# canusb.net
KiCad netlist of a schematic drawn in EAGLE
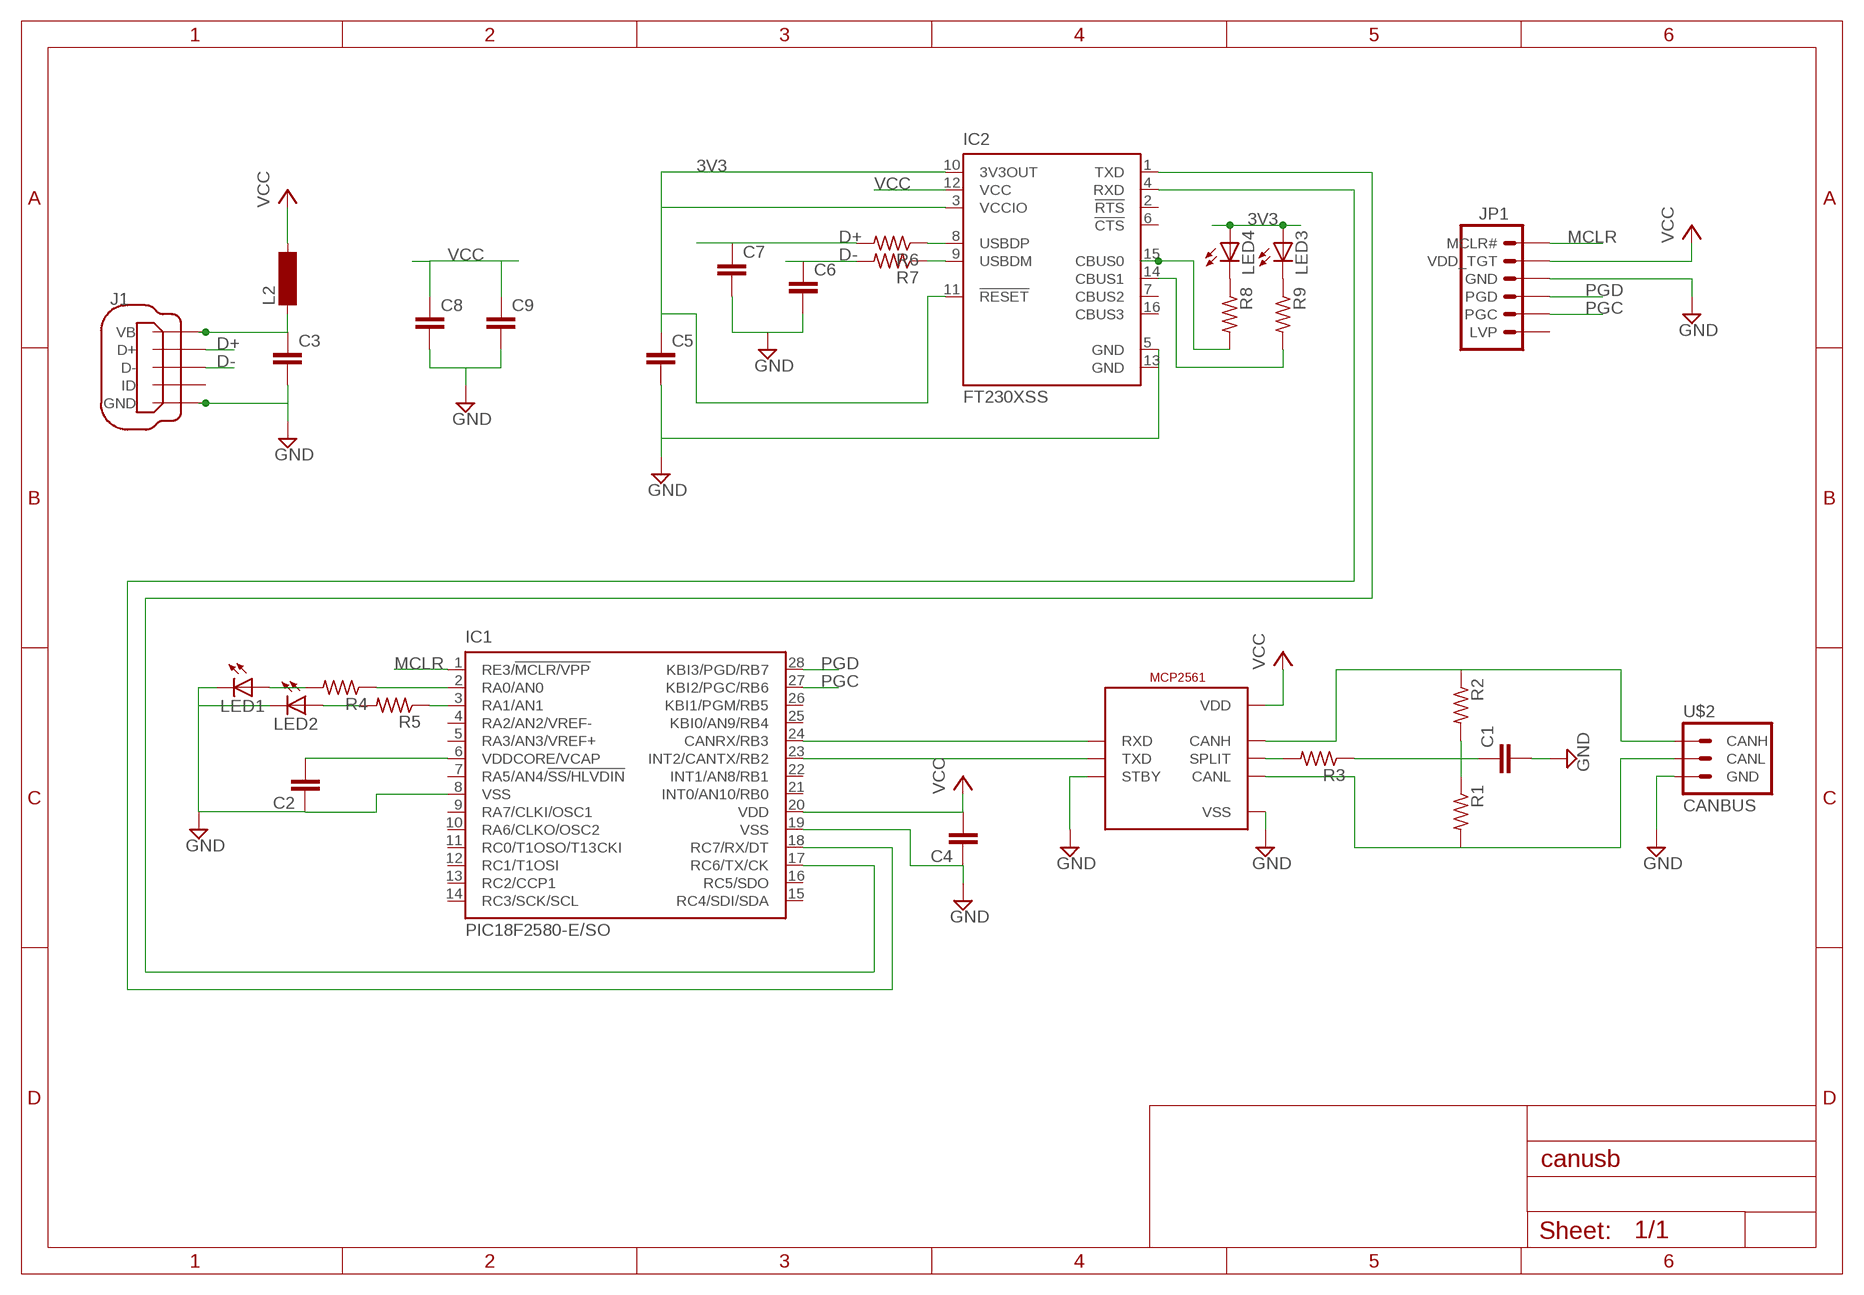
[diagram p0: schematic, sheet 1]

(export (version "E")
  (design (tool "Eeschema 10.0.6"))
  (components
    (comp (ref "C1")
      (value "C-EUC0805K")
      (footprint "eagle-import:C0805K")
      (libsource (lib "eagle-import") (part "C-EUC0805K"))
    )
    (comp (ref "C2")
      (value "C-EUC0805K")
      (footprint "eagle-import:C0805K")
      (libsource (lib "eagle-import") (part "C-EUC0805K"))
    )
    (comp (ref "C3")
      (value "C-EUC0805K")
      (footprint "eagle-import:C0805K")
      (libsource (lib "eagle-import") (part "C-EUC0805K"))
    )
    (comp (ref "C4")
      (value "C-EUC0805K")
      (footprint "eagle-import:C0805K")
      (libsource (lib "eagle-import") (part "C-EUC0805K"))
    )
    (comp (ref "C5")
      (value "C-EUC0805K")
      (footprint "eagle-import:C0805K")
      (libsource (lib "eagle-import") (part "C-EUC0805K"))
    )
    (comp (ref "C6")
      (value "C-EUC0805K")
      (footprint "eagle-import:C0805K")
      (libsource (lib "eagle-import") (part "C-EUC0805K"))
    )
    (comp (ref "C7")
      (value "C-EUC0805K")
      (footprint "eagle-import:C0805K")
      (libsource (lib "eagle-import") (part "C-EUC0805K"))
    )
    (comp (ref "C8")
      (value "C-EUC0805K")
      (footprint "eagle-import:C0805K")
      (libsource (lib "eagle-import") (part "C-EUC0805K"))
    )
    (comp (ref "C9")
      (value "C-EUC0805K")
      (footprint "eagle-import:C0805K")
      (libsource (lib "eagle-import") (part "C-EUC0805K"))
    )
    (comp (ref "IC1")
      (value "PIC18F2580-E/SO")
      (footprint "eagle-import:SO28W")
      (fields (field (name "MF") "MICROCHIP") (field (name "MPN") "PIC18F2580-I/SO"))
      (libsource (lib "eagle-import") (part "PIC18F280-E/SO5"))
    )
    (comp (ref "IC2")
      (value "FT230XSS")
      (footprint "eagle-import:SSOP16")
      (libsource (lib "eagle-import") (part "FT230XSS"))
    )
    (comp (ref "J1")
      (value "J_USB_MICROAB_HIROSE_ZX62-AB-5PA")
      (footprint "eagle-import:J_USB_MICROAB_HIROSE_ZX62-AB-5PA")
      (libsource (lib "eagle-import") (part "J_USB_MICROAB_HIROSE_ZX62-AB-5PA"))
    )
    (comp (ref "JP1")
      (value "ICSPLOCK")
      (footprint "eagle-import:1X06_LOCK")
      (libsource (lib "eagle-import") (part "ICSPLOCK"))
    )
    (comp (ref "L2")
      (value "FERRITE_BEAD")
      (footprint "eagle-import:R0805")
      (libsource (lib "eagle-import") (part "FERRITE_BEAD"))
    )
    (comp (ref "LED1")
      (value "LEDCHIPLED_0805")
      (footprint "eagle-import:CHIPLED_0805")
      (libsource (lib "eagle-import") (part "LEDCHIPLED_0805"))
    )
    (comp (ref "LED2")
      (value "LEDCHIPLED_0805")
      (footprint "eagle-import:CHIPLED_0805")
      (libsource (lib "eagle-import") (part "LEDCHIPLED_0805"))
    )
    (comp (ref "LED3")
      (value "LEDCHIPLED_0805")
      (footprint "eagle-import:CHIPLED_0805")
      (libsource (lib "eagle-import") (part "LEDCHIPLED_0805"))
    )
    (comp (ref "LED4")
      (value "LEDCHIPLED_0805")
      (footprint "eagle-import:CHIPLED_0805")
      (libsource (lib "eagle-import") (part "LEDCHIPLED_0805"))
    )
    (comp (ref "R1")
      (value "R-US_M0805")
      (footprint "eagle-import:M0805")
      (libsource (lib "eagle-import") (part "R-US_M0805"))
    )
    (comp (ref "R2")
      (value "R-US_M0805")
      (footprint "eagle-import:M0805")
      (libsource (lib "eagle-import") (part "R-US_M0805"))
    )
    (comp (ref "R3")
      (value "R-US_M0805")
      (footprint "eagle-import:M0805")
      (libsource (lib "eagle-import") (part "R-US_M0805"))
    )
    (comp (ref "R4")
      (value "R-US_M0805")
      (footprint "eagle-import:M0805")
      (libsource (lib "eagle-import") (part "R-US_M0805"))
    )
    (comp (ref "R5")
      (value "R-US_M0805")
      (footprint "eagle-import:M0805")
      (libsource (lib "eagle-import") (part "R-US_M0805"))
    )
    (comp (ref "R6")
      (value "R-US_M0805")
      (footprint "eagle-import:M0805")
      (libsource (lib "eagle-import") (part "R-US_M0805"))
    )
    (comp (ref "R7")
      (value "R-US_M0805")
      (footprint "eagle-import:M0805")
      (libsource (lib "eagle-import") (part "R-US_M0805"))
    )
    (comp (ref "R8")
      (value "R-US_M0805")
      (footprint "eagle-import:M0805")
      (libsource (lib "eagle-import") (part "R-US_M0805"))
    )
    (comp (ref "R9")
      (value "R-US_M0805")
      (footprint "eagle-import:M0805")
      (libsource (lib "eagle-import") (part "R-US_M0805"))
    )
    (comp (ref "U$1")
      (value "MCP2561")
      (footprint "eagle-import:SOIC8")
      (libsource (lib "eagle-import") (part "MCP2561"))
    )
    (comp (ref "U$2")
      (value "CANBUS")
      (footprint "eagle-import:MA03-1")
      (libsource (lib "eagle-import") (part "CANBUS"))
    )
  )
  (nets
    (net (code "1") (name "/3V3") (class "Default")
      (node (ref "C5") (pin "1") (pinfunction "1_1") (pintype "passive"))
      (node (ref "IC2") (pin "10") (pinfunction "3V3OUT_10") (pintype "output"))
      (node (ref "IC2") (pin "11") (pinfunction "~{RESET}_11") (pintype "input"))
      (node (ref "IC2") (pin "3") (pinfunction "VCCIO_3") (pintype "power_in"))
      (node (ref "LED3") (pin "A") (pinfunction "A_A") (pintype "passive"))
      (node (ref "LED4") (pin "A") (pinfunction "A_A") (pintype "passive"))
    )
    (net (code "2") (name "/D+") (class "Default")
      (node (ref "C7") (pin "1") (pinfunction "1_1") (pintype "passive"))
      (node (ref "J1") (pin "P$3") (pinfunction "D+_P$3") (pintype "passive"))
      (node (ref "R6") (pin "2") (pinfunction "2_2") (pintype "passive"))
    )
    (net (code "3") (name "/D-") (class "Default")
      (node (ref "C6") (pin "1") (pinfunction "1_1") (pintype "passive"))
      (node (ref "J1") (pin "P$2") (pinfunction "D-_P$2") (pintype "passive"))
      (node (ref "R7") (pin "2") (pinfunction "2_2") (pintype "passive"))
    )
    (net (code "4") (name "/MCLR") (class "Default")
      (node (ref "IC1") (pin "1") (pinfunction "RE3/~{MCLR/VPP}_1") (pintype "input"))
      (node (ref "JP1") (pin "1") (pinfunction "MCLR#_1") (pintype "passive"))
    )
    (net (code "5") (name "/PGC") (class "Default")
      (node (ref "IC1") (pin "27") (pinfunction "KBI2/PGC/RB6_27") (pintype "bidirectional"))
      (node (ref "JP1") (pin "5") (pinfunction "PGC_5") (pintype "passive"))
    )
    (net (code "6") (name "/PGD") (class "Default")
      (node (ref "IC1") (pin "28") (pinfunction "KBI3/PGD/RB7_28") (pintype "bidirectional"))
      (node (ref "JP1") (pin "4") (pinfunction "PGD_4") (pintype "passive"))
    )
    (net (code "7") (name "GND") (class "Default")
      (node (ref "C1") (pin "2") (pinfunction "2_2") (pintype "passive"))
      (node (ref "C2") (pin "1") (pinfunction "1_1") (pintype "passive"))
      (node (ref "C3") (pin "2") (pinfunction "2_2") (pintype "passive"))
      (node (ref "C4") (pin "1") (pinfunction "1_1") (pintype "passive"))
      (node (ref "C5") (pin "2") (pinfunction "2_2") (pintype "passive"))
      (node (ref "C6") (pin "2") (pinfunction "2_2") (pintype "passive"))
      (node (ref "C7") (pin "2") (pinfunction "2_2") (pintype "passive"))
      (node (ref "C8") (pin "2") (pinfunction "2_2") (pintype "passive"))
      (node (ref "C9") (pin "2") (pinfunction "2_2") (pintype "passive"))
      (node (ref "IC1") (pin "19") (pinfunction "VSS_19") (pintype "power_in"))
      (node (ref "IC1") (pin "8") (pinfunction "VSS_8") (pintype "power_in"))
      (node (ref "IC2") (pin "13") (pinfunction "GND_13") (pintype "power_in"))
      (node (ref "IC2") (pin "5") (pinfunction "GND_5") (pintype "power_in"))
      (node (ref "J1") (pin "P$5") (pinfunction "GND_P$5") (pintype "passive"))
      (node (ref "JP1") (pin "3") (pinfunction "GND_3") (pintype "passive"))
      (node (ref "LED1") (pin "C") (pinfunction "C_C") (pintype "passive"))
      (node (ref "LED2") (pin "C") (pinfunction "C_C") (pintype "passive"))
      (node (ref "U$1") (pin "P$2") (pinfunction "VSS_P$2") (pintype "bidirectional"))
      (node (ref "U$1") (pin "P$8") (pinfunction "STBY_P$8") (pintype "bidirectional"))
      (node (ref "U$2") (pin "3") (pinfunction "GND_3") (pintype "passive"))
    )
    (net (code "8") (name "Net-(C1-Pad1)") (class "Default")
      (node (ref "C1") (pin "1") (pinfunction "1_1") (pintype "passive"))
      (node (ref "R1") (pin "1") (pinfunction "1_1") (pintype "passive"))
      (node (ref "R2") (pin "2") (pinfunction "2_2") (pintype "passive"))
      (node (ref "R3") (pin "1") (pinfunction "1_1") (pintype "passive"))
    )
    (net (code "9") (name "Net-(IC1-CANRX{slash}RB3)") (class "Default")
      (node (ref "IC1") (pin "24") (pinfunction "CANRX/RB3_24") (pintype "bidirectional"))
      (node (ref "U$1") (pin "P$4") (pinfunction "RXD_P$4") (pintype "bidirectional"))
    )
    (net (code "10") (name "Net-(IC1-INT2{slash}CANTX{slash}RB2)") (class "Default")
      (node (ref "IC1") (pin "23") (pinfunction "INT2/CANTX/RB2_23") (pintype "bidirectional"))
      (node (ref "U$1") (pin "P$1") (pinfunction "TXD_P$1") (pintype "bidirectional"))
    )
    (net (code "11") (name "Net-(IC1-RA0{slash}AN0)") (class "Default")
      (node (ref "IC1") (pin "2") (pinfunction "RA0/AN0_2") (pintype "bidirectional"))
      (node (ref "R4") (pin "1") (pinfunction "1_1") (pintype "passive"))
    )
    (net (code "12") (name "Net-(IC1-RA1{slash}AN1)") (class "Default")
      (node (ref "IC1") (pin "3") (pinfunction "RA1/AN1_3") (pintype "bidirectional"))
      (node (ref "R5") (pin "1") (pinfunction "1_1") (pintype "passive"))
    )
    (net (code "13") (name "Net-(IC1-RC6{slash}TX{slash}CK)") (class "Default")
      (node (ref "IC1") (pin "17") (pinfunction "RC6/TX/CK_17") (pintype "bidirectional"))
      (node (ref "IC2") (pin "1") (pinfunction "TXD_1") (pintype "output"))
    )
    (net (code "14") (name "Net-(IC1-RC7{slash}RX{slash}DT)") (class "Default")
      (node (ref "IC1") (pin "18") (pinfunction "RC7/RX/DT_18") (pintype "bidirectional"))
      (node (ref "IC2") (pin "4") (pinfunction "RXD_4") (pintype "input"))
    )
    (net (code "15") (name "Net-(IC1-VDDCORE{slash}VCAP)") (class "Default")
      (node (ref "C2") (pin "2") (pinfunction "2_2") (pintype "passive"))
      (node (ref "IC1") (pin "6") (pinfunction "VDDCORE/VCAP_6") (pintype "bidirectional"))
    )
    (net (code "16") (name "Net-(IC2-CBUS0)") (class "Default")
      (node (ref "IC2") (pin "15") (pinfunction "CBUS0_15") (pintype "bidirectional"))
      (node (ref "R8") (pin "2") (pinfunction "2_2") (pintype "passive"))
    )
    (net (code "17") (name "Net-(IC2-CBUS1)") (class "Default")
      (node (ref "IC2") (pin "14") (pinfunction "CBUS1_14") (pintype "bidirectional"))
      (node (ref "R9") (pin "2") (pinfunction "2_2") (pintype "passive"))
    )
    (net (code "18") (name "Net-(IC2-USBDM)") (class "Default")
      (node (ref "IC2") (pin "9") (pinfunction "USBDM_9") (pintype "input"))
      (node (ref "R7") (pin "1") (pinfunction "1_1") (pintype "passive"))
    )
    (net (code "19") (name "Net-(IC2-USBDP)") (class "Default")
      (node (ref "IC2") (pin "8") (pinfunction "USBDP_8") (pintype "input"))
      (node (ref "R6") (pin "1") (pinfunction "1_1") (pintype "passive"))
    )
    (net (code "20") (name "Net-(J1-VB)") (class "Default")
      (node (ref "C3") (pin "1") (pinfunction "1_1") (pintype "passive"))
      (node (ref "J1") (pin "P$1") (pinfunction "VB_P$1") (pintype "passive"))
      (node (ref "L2") (pin "1") (pinfunction "1_1") (pintype "passive"))
    )
    (net (code "21") (name "Net-(LED1-PadA)") (class "Default")
      (node (ref "LED1") (pin "A") (pinfunction "A_A") (pintype "passive"))
      (node (ref "R4") (pin "2") (pinfunction "2_2") (pintype "passive"))
    )
    (net (code "22") (name "Net-(LED2-PadA)") (class "Default")
      (node (ref "LED2") (pin "A") (pinfunction "A_A") (pintype "passive"))
      (node (ref "R5") (pin "2") (pinfunction "2_2") (pintype "passive"))
    )
    (net (code "23") (name "Net-(LED3-PadC)") (class "Default")
      (node (ref "LED3") (pin "C") (pinfunction "C_C") (pintype "passive"))
      (node (ref "R9") (pin "1") (pinfunction "1_1") (pintype "passive"))
    )
    (net (code "24") (name "Net-(LED4-PadC)") (class "Default")
      (node (ref "LED4") (pin "C") (pinfunction "C_C") (pintype "passive"))
      (node (ref "R8") (pin "1") (pinfunction "1_1") (pintype "passive"))
    )
    (net (code "25") (name "Net-(U$1-CANH)") (class "Default")
      (node (ref "R2") (pin "1") (pinfunction "1_1") (pintype "passive"))
      (node (ref "U$1") (pin "P$7") (pinfunction "CANH_P$7") (pintype "bidirectional"))
      (node (ref "U$2") (pin "1") (pinfunction "CANH_1") (pintype "passive"))
    )
    (net (code "26") (name "Net-(U$1-CANL)") (class "Default")
      (node (ref "R1") (pin "2") (pinfunction "2_2") (pintype "passive"))
      (node (ref "U$1") (pin "P$6") (pinfunction "CANL_P$6") (pintype "bidirectional"))
      (node (ref "U$2") (pin "2") (pinfunction "CANL_2") (pintype "passive"))
    )
    (net (code "27") (name "Net-(U$1-SPLIT)") (class "Default")
      (node (ref "R3") (pin "2") (pinfunction "2_2") (pintype "passive"))
      (node (ref "U$1") (pin "P$5") (pinfunction "SPLIT_P$5") (pintype "bidirectional"))
    )
    (net (code "28") (name "VCC") (class "Default")
      (node (ref "C4") (pin "2") (pinfunction "2_2") (pintype "passive"))
      (node (ref "C8") (pin "1") (pinfunction "1_1") (pintype "passive"))
      (node (ref "C9") (pin "1") (pinfunction "1_1") (pintype "passive"))
      (node (ref "IC1") (pin "20") (pinfunction "VDD_20") (pintype "power_in"))
      (node (ref "IC2") (pin "12") (pinfunction "VCC_12") (pintype "power_in"))
      (node (ref "JP1") (pin "2") (pinfunction "VDD_TGT_2") (pintype "passive"))
      (node (ref "L2") (pin "2") (pinfunction "2_2") (pintype "passive"))
      (node (ref "U$1") (pin "P$3") (pinfunction "VDD_P$3") (pintype "bidirectional"))
    )
    (net (code "29") (name "unconnected-(IC1-INT0{slash}AN10{slash}RB0-Pad21)") (class "Default")
      (node (ref "IC1") (pin "21") (pinfunction "INT0/AN10/RB0_21") (pintype "bidirectional"))
    )
    (net (code "30") (name "unconnected-(IC1-INT1{slash}AN8{slash}RB1-Pad22)") (class "Default")
      (node (ref "IC1") (pin "22") (pinfunction "INT1/AN8/RB1_22") (pintype "bidirectional"))
    )
    (net (code "31") (name "unconnected-(IC1-KBI0{slash}AN9{slash}RB4-Pad25)") (class "Default")
      (node (ref "IC1") (pin "25") (pinfunction "KBI0/AN9/RB4_25") (pintype "bidirectional"))
    )
    (net (code "32") (name "unconnected-(IC1-KBI1{slash}PGM{slash}RB5-Pad26)") (class "Default")
      (node (ref "IC1") (pin "26") (pinfunction "KBI1/PGM/RB5_26") (pintype "bidirectional"))
    )
    (net (code "33") (name "unconnected-(IC1-RA2{slash}AN2{slash}VREF--Pad4)") (class "Default")
      (node (ref "IC1") (pin "4") (pinfunction "RA2/AN2/VREF-_4") (pintype "bidirectional"))
    )
    (net (code "34") (name "unconnected-(IC1-RA3{slash}AN3{slash}VREF+-Pad5)") (class "Default")
      (node (ref "IC1") (pin "5") (pinfunction "RA3/AN3/VREF+_5") (pintype "bidirectional"))
    )
    (net (code "35") (name "unconnected-(IC1-RA5{slash}AN4{slash}~{SS{slash}HLVDIN}-Pad7)") (class "Default")
      (node (ref "IC1") (pin "7") (pinfunction "RA5/AN4/~{SS/HLVDIN}_7") (pintype "bidirectional"))
    )
    (net (code "36") (name "unconnected-(IC1-RA6{slash}CLKO{slash}OSC2-Pad10)") (class "Default")
      (node (ref "IC1") (pin "10") (pinfunction "RA6/CLKO/OSC2_10") (pintype "output"))
    )
    (net (code "37") (name "unconnected-(IC1-RA7{slash}CLKI{slash}OSC1-Pad9)") (class "Default")
      (node (ref "IC1") (pin "9") (pinfunction "RA7/CLKI/OSC1_9") (pintype "input"))
    )
    (net (code "38") (name "unconnected-(IC1-RC0{slash}T1OSO{slash}T13CKI-Pad11)") (class "Default")
      (node (ref "IC1") (pin "11") (pinfunction "RC0/T1OSO/T13CKI_11") (pintype "bidirectional"))
    )
    (net (code "39") (name "unconnected-(IC1-RC1{slash}T1OSI-Pad12)") (class "Default")
      (node (ref "IC1") (pin "12") (pinfunction "RC1/T1OSI_12") (pintype "bidirectional"))
    )
    (net (code "40") (name "unconnected-(IC1-RC2{slash}CCP1-Pad13)") (class "Default")
      (node (ref "IC1") (pin "13") (pinfunction "RC2/CCP1_13") (pintype "bidirectional"))
    )
    (net (code "41") (name "unconnected-(IC1-RC3{slash}SCK{slash}SCL-Pad14)") (class "Default")
      (node (ref "IC1") (pin "14") (pinfunction "RC3/SCK/SCL_14") (pintype "bidirectional"))
    )
    (net (code "42") (name "unconnected-(IC1-RC4{slash}SDI{slash}SDA-Pad15)") (class "Default")
      (node (ref "IC1") (pin "15") (pinfunction "RC4/SDI/SDA_15") (pintype "bidirectional"))
    )
    (net (code "43") (name "unconnected-(IC1-RC5{slash}SDO-Pad16)") (class "Default")
      (node (ref "IC1") (pin "16") (pinfunction "RC5/SDO_16") (pintype "bidirectional"))
    )
    (net (code "44") (name "unconnected-(IC2-CBUS2-Pad7)") (class "Default")
      (node (ref "IC2") (pin "7") (pinfunction "CBUS2_7") (pintype "bidirectional"))
    )
    (net (code "45") (name "unconnected-(IC2-CBUS3-Pad16)") (class "Default")
      (node (ref "IC2") (pin "16") (pinfunction "CBUS3_16") (pintype "bidirectional"))
    )
    (net (code "46") (name "unconnected-(IC2-~{CTS}-Pad6)") (class "Default")
      (node (ref "IC2") (pin "6") (pinfunction "~{CTS}_6") (pintype "input"))
    )
    (net (code "47") (name "unconnected-(IC2-~{RTS}-Pad2)") (class "Default")
      (node (ref "IC2") (pin "2") (pinfunction "~{RTS}_2") (pintype "output"))
    )
    (net (code "48") (name "unconnected-(J1-ID-PadP$4)") (class "Default")
      (node (ref "J1") (pin "P$4") (pinfunction "ID_P$4") (pintype "passive"))
    )
    (net (code "49") (name "unconnected-(JP1-LVP-Pad6)") (class "Default")
      (node (ref "JP1") (pin "6") (pinfunction "LVP_6") (pintype "passive"))
    )
  )
)
